# FETSwitch.net
KiCad netlist of a schematic drawn in EAGLE
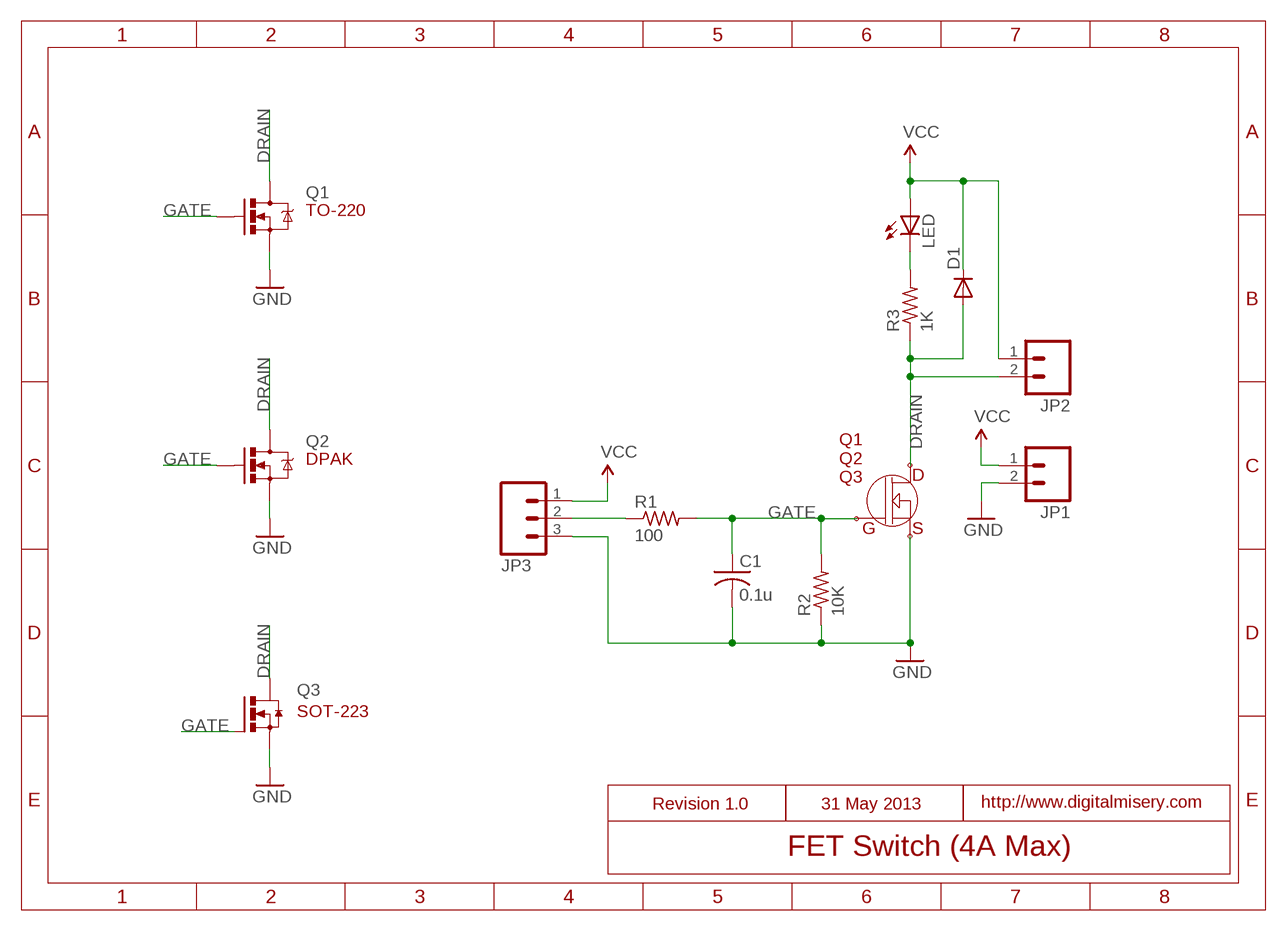
[diagram p0: schematic, sheet 1]

(export (version "E")
  (design (tool "Eeschema 10.0.6"))
  (components
    (comp (ref "C1")
      (value "0.1u")
      (footprint "eagle-import:C0805K")
      (libsource (lib "eagle-import") (part "C-USC0805K"))
    )
    (comp (ref "D1")
      (value "DIODESMA")
      (footprint "eagle-import:SMA-DIODE")
      (libsource (lib "eagle-import") (part "DIODESMA"))
    )
    (comp (ref "JP1")
      (value "M02PTH3")
      (footprint "eagle-import:1X02_LONGPADS")
      (libsource (lib "eagle-import") (part "M02PTH3"))
    )
    (comp (ref "JP2")
      (value "M02PTH3")
      (footprint "eagle-import:1X02_LONGPADS")
      (libsource (lib "eagle-import") (part "M02PTH3"))
    )
    (comp (ref "JP3")
      (value "M03LONGPADS")
      (footprint "eagle-import:1X03_LONGPADS")
      (libsource (lib "eagle-import") (part "M03LONGPADS"))
    )
    (comp (ref "LED")
      (value "LEDCHIP-LED0805")
      (footprint "eagle-import:CHIP-LED0805")
      (libsource (lib "eagle-import") (part "LEDCHIP-LED0805"))
    )
    (comp (ref "Q1")
      (value "MOSFET-NCHANNELFQP30N06L")
      (footprint "eagle-import:TO220V")
      (libsource (lib "eagle-import") (part "MOSFET-NCHANNELFQP30N06L"))
    )
    (comp (ref "Q2")
      (value "MOSFET-NCHANNELFDD8780")
      (footprint "eagle-import:DPAK")
      (libsource (lib "eagle-import") (part "MOSFET-NCHANNELFDD8780"))
    )
    (comp (ref "Q3")
      (value "N-HEXFET-2D_SOT232-")
      (footprint "eagle-import:SOT223")
      (libsource (lib "eagle-import") (part "N-HEXFET-2D_?-SOT232"))
    )
    (comp (ref "R1")
      (value "100")
      (footprint "eagle-import:R0805")
      (libsource (lib "eagle-import") (part "R-US_R0805"))
    )
    (comp (ref "R2")
      (value "10K")
      (footprint "eagle-import:R0805")
      (libsource (lib "eagle-import") (part "R-US_R0805"))
    )
    (comp (ref "R3")
      (value "1K")
      (footprint "eagle-import:R0805")
      (libsource (lib "eagle-import") (part "R-US_R0805"))
    )
  )
  (nets
    (net (code "1") (name "/DRAIN") (class "Default")
      (node (ref "D1") (pin "A") (pinfunction "A_A") (pintype "passive"))
      (node (ref "JP2") (pin "2") (pinfunction "2_2") (pintype "passive"))
      (node (ref "Q1") (pin "2") (pinfunction "D_2") (pintype "passive"))
      (node (ref "Q2") (pin "4") (pinfunction "D_4") (pintype "passive"))
      (node (ref "Q3") (pin "2") (pinfunction "D_2") (pintype "passive"))
      (node (ref "Q3") (pin "4") (pinfunction "D_4") (pintype "passive"))
      (node (ref "R3") (pin "1") (pinfunction "1_1") (pintype "passive"))
    )
    (net (code "2") (name "/GATE") (class "Default")
      (node (ref "C1") (pin "1") (pinfunction "1_1") (pintype "passive"))
      (node (ref "Q1") (pin "1") (pinfunction "G_1") (pintype "passive"))
      (node (ref "Q2") (pin "1") (pinfunction "G_1") (pintype "passive"))
      (node (ref "Q3") (pin "1") (pinfunction "G_1") (pintype "passive"))
      (node (ref "R1") (pin "2") (pinfunction "2_2") (pintype "passive"))
      (node (ref "R2") (pin "2") (pinfunction "2_2") (pintype "passive"))
    )
    (net (code "3") (name "GND") (class "Default")
      (node (ref "C1") (pin "2") (pinfunction "2_2") (pintype "passive"))
      (node (ref "JP1") (pin "2") (pinfunction "2_2") (pintype "passive"))
      (node (ref "JP3") (pin "3") (pinfunction "3_3") (pintype "passive"))
      (node (ref "Q1") (pin "3") (pinfunction "S_3") (pintype "passive"))
      (node (ref "Q2") (pin "3") (pinfunction "S_3") (pintype "passive"))
      (node (ref "Q3") (pin "3") (pinfunction "S_3") (pintype "passive"))
      (node (ref "R2") (pin "1") (pinfunction "1_1") (pintype "passive"))
    )
    (net (code "4") (name "Net-(JP3-Pad2)") (class "Default")
      (node (ref "JP3") (pin "2") (pinfunction "2_2") (pintype "passive"))
      (node (ref "R1") (pin "1") (pinfunction "1_1") (pintype "passive"))
    )
    (net (code "5") (name "Net-(LED-PadC)") (class "Default")
      (node (ref "LED") (pin "C") (pinfunction "C_C") (pintype "passive"))
      (node (ref "R3") (pin "2") (pinfunction "2_2") (pintype "passive"))
    )
    (net (code "6") (name "VCC") (class "Default")
      (node (ref "D1") (pin "C") (pinfunction "C_C") (pintype "passive"))
      (node (ref "JP1") (pin "1") (pinfunction "1_1") (pintype "passive"))
      (node (ref "JP2") (pin "1") (pinfunction "1_1") (pintype "passive"))
      (node (ref "JP3") (pin "1") (pinfunction "1_1") (pintype "passive"))
      (node (ref "LED") (pin "A") (pinfunction "A_A") (pintype "passive"))
    )
  )
)
